# PiBladePsuInput.net
KiCad netlist of a schematic drawn in EAGLE
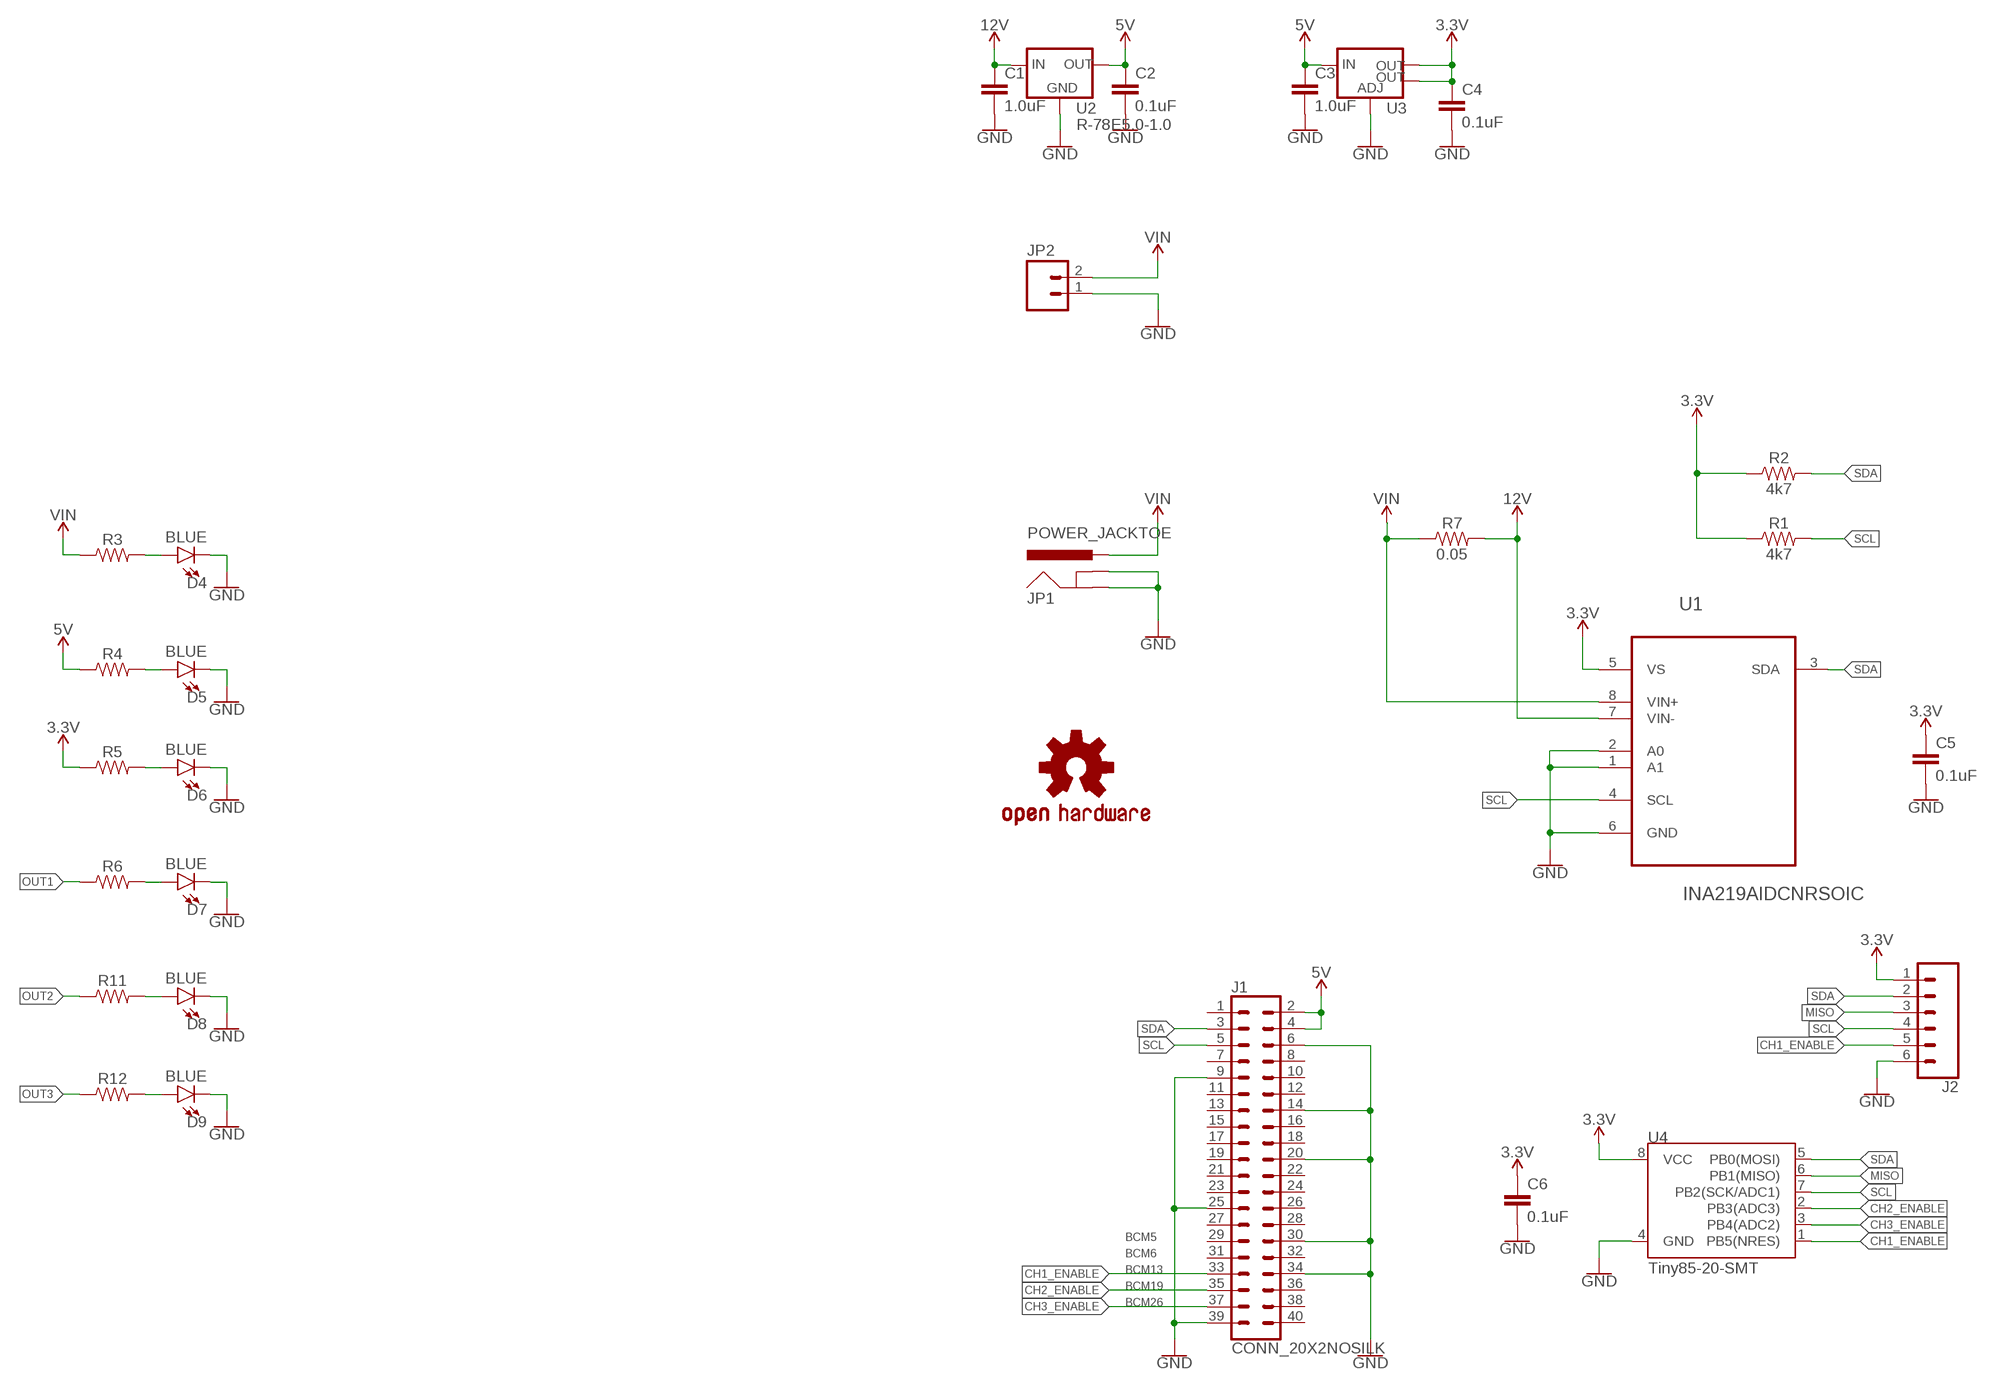
[diagram p0: schematic, sheet 1, part 1 of 2]
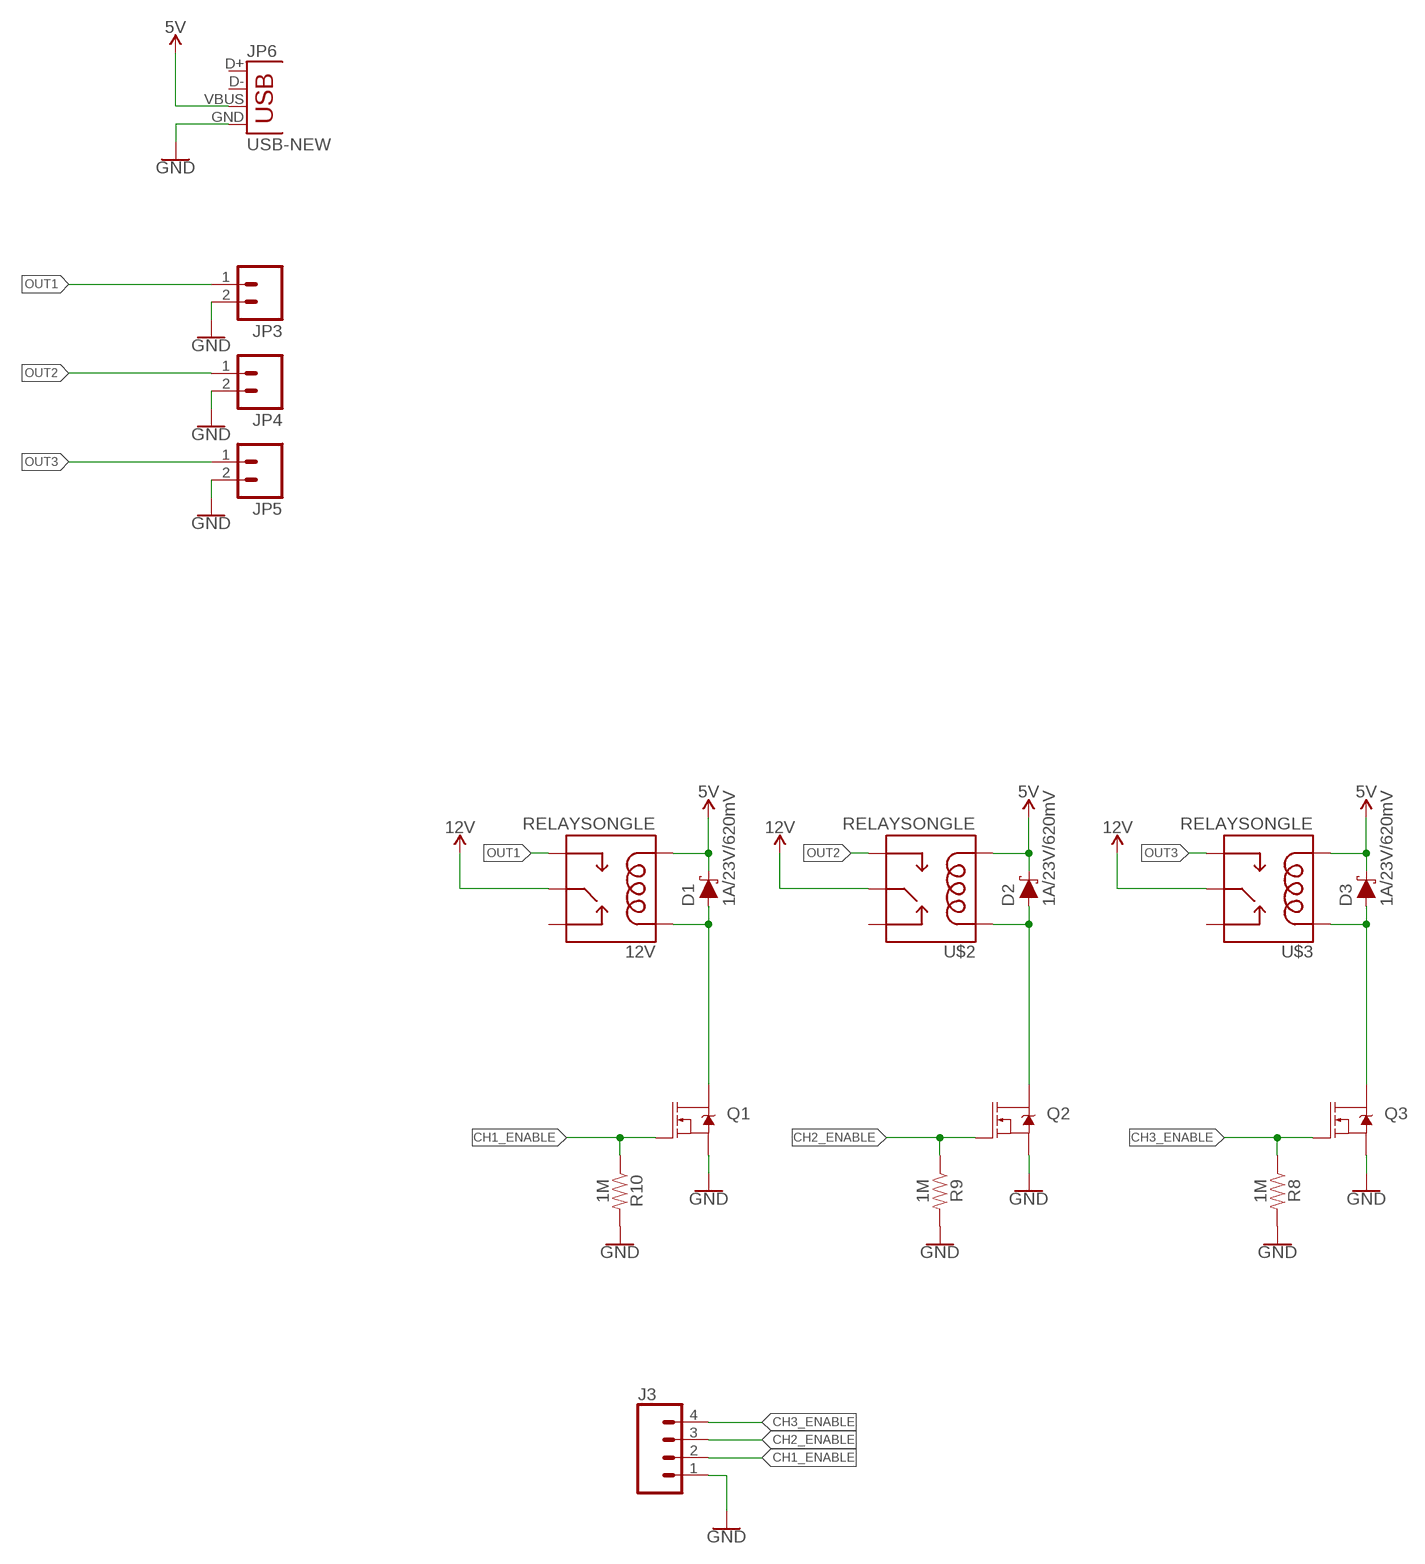
[diagram p1: schematic, sheet 1, part 2 of 2]

(export (version "E")
  (design (tool "Eeschema 10.0.6"))
  (components
    (comp (ref "12V")
      (value "RELAYSONGLE")
      (footprint "eagle-import:SRD-5VDC-SL-C")
      (libsource (lib "eagle-import") (part "RELAYSONGLE"))
    )
    (comp (ref "C1")
      (value "1.0uF")
      (footprint "eagle-import:0805")
      (libsource (lib "eagle-import") (part "1.0UF-0805-25V-(+80/-20%)"))
    )
    (comp (ref "C2")
      (value "0.1uF")
      (footprint "eagle-import:0805")
      (libsource (lib "eagle-import") (part "1.0UF-0805-25V-(+80/-20%)"))
    )
    (comp (ref "C3")
      (value "1.0uF")
      (footprint "eagle-import:0805")
      (libsource (lib "eagle-import") (part "1.0UF-0805-25V-(+80/-20%)"))
    )
    (comp (ref "C4")
      (value "0.1uF")
      (footprint "eagle-import:0805")
      (libsource (lib "eagle-import") (part "1.0UF-0805-25V-(+80/-20%)"))
    )
    (comp (ref "C5")
      (value "0.1uF")
      (footprint "eagle-import:0805")
      (libsource (lib "eagle-import") (part "1.0UF-0805-25V-(+80/-20%)"))
    )
    (comp (ref "C6")
      (value "0.1uF")
      (footprint "eagle-import:0805")
      (libsource (lib "eagle-import") (part "1.0UF-0805-25V-(+80/-20%)"))
    )
    (comp (ref "D1")
      (value "1A/23V/620mV")
      (footprint "eagle-import:SOD-323")
      (libsource (lib "eagle-import") (part "DIODE-SCHOTTKY-BAT20J"))
    )
    (comp (ref "D2")
      (value "1A/23V/620mV")
      (footprint "eagle-import:SOD-323")
      (libsource (lib "eagle-import") (part "DIODE-SCHOTTKY-BAT20J"))
    )
    (comp (ref "D3")
      (value "1A/23V/620mV")
      (footprint "eagle-import:SOD-323")
      (libsource (lib "eagle-import") (part "DIODE-SCHOTTKY-BAT20J"))
    )
    (comp (ref "D4")
      (value "BLUE")
      (footprint "eagle-import:LED-1206")
      (libsource (lib "eagle-import") (part "LED-BLUE1206"))
    )
    (comp (ref "D5")
      (value "BLUE")
      (footprint "eagle-import:LED-1206")
      (libsource (lib "eagle-import") (part "LED-BLUE1206"))
    )
    (comp (ref "D6")
      (value "BLUE")
      (footprint "eagle-import:LED-1206")
      (libsource (lib "eagle-import") (part "LED-BLUE1206"))
    )
    (comp (ref "D7")
      (value "BLUE")
      (footprint "eagle-import:LED-1206")
      (libsource (lib "eagle-import") (part "LED-BLUE1206"))
    )
    (comp (ref "D8")
      (value "BLUE")
      (footprint "eagle-import:LED-1206")
      (libsource (lib "eagle-import") (part "LED-BLUE1206"))
    )
    (comp (ref "D9")
      (value "BLUE")
      (footprint "eagle-import:LED-1206")
      (libsource (lib "eagle-import") (part "LED-BLUE1206"))
    )
    (comp (ref "J1")
      (value "CONN_20X2NOSILK")
      (footprint "eagle-import:2X20_NOSILK")
      (libsource (lib "eagle-import") (part "CONN_20X2NOSILK"))
    )
    (comp (ref "J2")
      (value "CONN_06SMD-1MM")
      (footprint "eagle-import:1X06-1MM")
      (libsource (lib "eagle-import") (part "CONN_06SMD-1MM"))
    )
    (comp (ref "J3")
      (value "CONN_04SMD2")
      (footprint "eagle-import:1X04_1MM_RA")
      (libsource (lib "eagle-import") (part "CONN_04SMD2"))
    )
    (comp (ref "JP1")
      (value "POWER_JACKTOE")
      (footprint "eagle-import:POWER_JACK_SMD_OVERPASTE_TOE")
      (libsource (lib "eagle-import") (part "POWER_JACKTOE"))
    )
    (comp (ref "JP2")
      (value "M025MM")
      (footprint "eagle-import:SCREWTERMINAL-5MM-2")
      (libsource (lib "eagle-import") (part "M025MM"))
    )
    (comp (ref "JP3")
      (value "M025MM")
      (footprint "eagle-import:SCREWTERMINAL-5MM-2")
      (libsource (lib "eagle-import") (part "M025MM"))
    )
    (comp (ref "JP4")
      (value "M025MM")
      (footprint "eagle-import:SCREWTERMINAL-5MM-2")
      (libsource (lib "eagle-import") (part "M025MM"))
    )
    (comp (ref "JP5")
      (value "M025MM")
      (footprint "eagle-import:SCREWTERMINAL-5MM-2")
      (libsource (lib "eagle-import") (part "M025MM"))
    )
    (comp (ref "JP6")
      (value "USB-NEW")
      (footprint "eagle-import:USB-A-VERTICAL")
      (libsource (lib "eagle-import") (part "USB-NEW"))
    )
    (comp (ref "LOGO1")
      (value "OSHW-LOGOM")
      (footprint "eagle-import:OSHW-LOGO-M")
      (libsource (lib "eagle-import") (part "OSHW-LOGOM"))
    )
    (comp (ref "Q1")
      (value "220mA/50V/3.5Ω")
      (footprint "eagle-import:SOT23-3")
      (libsource (lib "eagle-import") (part "MOSFET-NCH-BSS138"))
    )
    (comp (ref "Q2")
      (value "220mA/50V/3.5Ω")
      (footprint "eagle-import:SOT23-3")
      (libsource (lib "eagle-import") (part "MOSFET-NCH-BSS138"))
    )
    (comp (ref "Q3")
      (value "220mA/50V/3.5Ω")
      (footprint "eagle-import:SOT23-3")
      (libsource (lib "eagle-import") (part "MOSFET-NCH-BSS138"))
    )
    (comp (ref "R1")
      (value "4k7")
      (footprint "eagle-import:0805")
      (libsource (lib "eagle-import") (part "RESISTOR0805"))
    )
    (comp (ref "R2")
      (value "4k7")
      (footprint "eagle-import:0805")
      (libsource (lib "eagle-import") (part "RESISTOR0805"))
    )
    (comp (ref "R3")
      (value "RESISTOR0805")
      (footprint "eagle-import:0805")
      (libsource (lib "eagle-import") (part "RESISTOR0805"))
    )
    (comp (ref "R4")
      (value "RESISTOR0805")
      (footprint "eagle-import:0805")
      (libsource (lib "eagle-import") (part "RESISTOR0805"))
    )
    (comp (ref "R5")
      (value "RESISTOR0805")
      (footprint "eagle-import:0805")
      (libsource (lib "eagle-import") (part "RESISTOR0805"))
    )
    (comp (ref "R6")
      (value "RESISTOR0805")
      (footprint "eagle-import:0805")
      (libsource (lib "eagle-import") (part "RESISTOR0805"))
    )
    (comp (ref "R7")
      (value "0.05")
      (footprint "eagle-import:2512")
      (libsource (lib "eagle-import") (part "0.05OHM-2512-3W-1%"))
    )
    (comp (ref "R8")
      (value "1M")
      (footprint "eagle-import:0805")
      (libsource (lib "eagle-import") (part "RESISTOR0805"))
    )
    (comp (ref "R9")
      (value "1M")
      (footprint "eagle-import:0805")
      (libsource (lib "eagle-import") (part "RESISTOR0805"))
    )
    (comp (ref "R10")
      (value "1M")
      (footprint "eagle-import:0805")
      (libsource (lib "eagle-import") (part "RESISTOR0805"))
    )
    (comp (ref "R11")
      (value "RESISTOR0805")
      (footprint "eagle-import:0805")
      (libsource (lib "eagle-import") (part "RESISTOR0805"))
    )
    (comp (ref "R12")
      (value "RESISTOR0805")
      (footprint "eagle-import:0805")
      (libsource (lib "eagle-import") (part "RESISTOR0805"))
    )
    (comp (ref "U$2")
      (value "RELAYSONGLE")
      (footprint "eagle-import:SRD-5VDC-SL-C")
      (libsource (lib "eagle-import") (part "RELAYSONGLE"))
    )
    (comp (ref "U$3")
      (value "RELAYSONGLE")
      (footprint "eagle-import:SRD-5VDC-SL-C")
      (libsource (lib "eagle-import") (part "RELAYSONGLE"))
    )
    (comp (ref "U1")
      (value "INA219AIDCNRSOIC")
      (footprint "eagle-import:SO08")
      (libsource (lib "eagle-import") (part "INA219AIDCNRSOIC"))
    )
    (comp (ref "U2")
      (value "R-78E5.0-1.0")
      (footprint "eagle-import:DC-DC_CONVERTER_78XX")
      (libsource (lib "eagle-import") (part "R-78E5.0-1.0"))
    )
    (comp (ref "U3")
      (value "V_REG_LM1117SOT223")
      (footprint "eagle-import:SOT223")
      (libsource (lib "eagle-import") (part "V_REG_LM1117SOT223"))
    )
    (comp (ref "U4")
      (value "Tiny85-20-SMT")
      (footprint "eagle-import:SO08-EIAJ")
      (libsource (lib "eagle-import") (part "ATTINY45TINY85-20-SMT"))
    )
  )
  (nets
    (net (code "1") (name "3.3V") (class "Default")
      (node (ref "C4") (pin "1") (pinfunction "1_1") (pintype "passive"))
      (node (ref "C5") (pin "1") (pinfunction "1_1") (pintype "passive"))
      (node (ref "C6") (pin "1") (pinfunction "1_1") (pintype "passive"))
      (node (ref "J2") (pin "1") (pinfunction "1_1") (pintype "passive"))
      (node (ref "R1") (pin "1") (pinfunction "1_1") (pintype "passive"))
      (node (ref "R2") (pin "1") (pinfunction "1_1") (pintype "passive"))
      (node (ref "R5") (pin "1") (pinfunction "1_1") (pintype "passive"))
      (node (ref "U1") (pin "5") (pinfunction "VS_5") (pintype "power_in"))
      (node (ref "U3") (pin "2") (pinfunction "OUT_2") (pintype "output"))
      (node (ref "U3") (pin "4") (pinfunction "OUT_4") (pintype "output"))
      (node (ref "U4") (pin "8") (pinfunction "VCC_8") (pintype "bidirectional"))
    )
    (net (code "2") (name "5V") (class "Default")
      (node (ref "12V") (pin "COIL2") (pinfunction "COIL2_COIL2") (pintype "bidirectional"))
      (node (ref "C2") (pin "1") (pinfunction "1_1") (pintype "passive"))
      (node (ref "C3") (pin "1") (pinfunction "1_1") (pintype "passive"))
      (node (ref "D1") (pin "C") (pinfunction "C_C") (pintype "passive"))
      (node (ref "D2") (pin "C") (pinfunction "C_C") (pintype "passive"))
      (node (ref "D3") (pin "C") (pinfunction "C_C") (pintype "passive"))
      (node (ref "J1") (pin "2") (pinfunction "2_2") (pintype "passive"))
      (node (ref "J1") (pin "4") (pinfunction "4_4") (pintype "passive"))
      (node (ref "JP6") (pin "VBUS") (pinfunction "VBUS_VBUS") (pintype "bidirectional"))
      (node (ref "R4") (pin "1") (pinfunction "1_1") (pintype "passive"))
      (node (ref "U$2") (pin "COIL2") (pinfunction "COIL2_COIL2") (pintype "bidirectional"))
      (node (ref "U$3") (pin "COIL2") (pinfunction "COIL2_COIL2") (pintype "bidirectional"))
      (node (ref "U2") (pin "VOUT") (pinfunction "OUT_VOUT") (pintype "passive"))
      (node (ref "U3") (pin "3") (pinfunction "IN_3") (pintype "input"))
    )
    (net (code "3") (name "12V") (class "Default")
      (node (ref "12V") (pin "COMMON") (pinfunction "MAIN_COMMON") (pintype "bidirectional"))
      (node (ref "C1") (pin "1") (pinfunction "1_1") (pintype "passive"))
      (node (ref "R7") (pin "P$2") (pinfunction "2_P$2") (pintype "passive"))
      (node (ref "U$2") (pin "COMMON") (pinfunction "MAIN_COMMON") (pintype "bidirectional"))
      (node (ref "U$3") (pin "COMMON") (pinfunction "MAIN_COMMON") (pintype "bidirectional"))
      (node (ref "U1") (pin "7") (pinfunction "VIN-_7") (pintype "input"))
      (node (ref "U2") (pin "VIN") (pinfunction "IN_VIN") (pintype "input"))
    )
    (net (code "4") (name "CH1_ENABLE") (class "Default")
      (node (ref "J1") (pin "33") (pinfunction "33_33") (pintype "passive"))
      (node (ref "J2") (pin "5") (pinfunction "5_5") (pintype "passive"))
      (node (ref "J3") (pin "2") (pinfunction "2_2") (pintype "passive"))
      (node (ref "Q1") (pin "1") (pinfunction "G_1") (pintype "bidirectional"))
      (node (ref "R10") (pin "1") (pinfunction "1_1") (pintype "passive"))
      (node (ref "U4") (pin "1") (pinfunction "PB5(NRES)_1") (pintype "bidirectional"))
    )
    (net (code "5") (name "CH2_ENABLE") (class "Default")
      (node (ref "J1") (pin "35") (pinfunction "35_35") (pintype "passive"))
      (node (ref "J3") (pin "3") (pinfunction "3_3") (pintype "passive"))
      (node (ref "Q2") (pin "1") (pinfunction "G_1") (pintype "bidirectional"))
      (node (ref "R9") (pin "1") (pinfunction "1_1") (pintype "passive"))
      (node (ref "U4") (pin "2") (pinfunction "PB3(ADC3)_2") (pintype "bidirectional"))
    )
    (net (code "6") (name "CH3_ENABLE") (class "Default")
      (node (ref "J1") (pin "37") (pinfunction "37_37") (pintype "passive"))
      (node (ref "J3") (pin "4") (pinfunction "4_4") (pintype "passive"))
      (node (ref "Q3") (pin "1") (pinfunction "G_1") (pintype "bidirectional"))
      (node (ref "R8") (pin "1") (pinfunction "1_1") (pintype "passive"))
      (node (ref "U4") (pin "3") (pinfunction "PB4(ADC2)_3") (pintype "bidirectional"))
    )
    (net (code "7") (name "GND") (class "Default")
      (node (ref "C1") (pin "2") (pinfunction "2_2") (pintype "passive"))
      (node (ref "C2") (pin "2") (pinfunction "2_2") (pintype "passive"))
      (node (ref "C3") (pin "2") (pinfunction "2_2") (pintype "passive"))
      (node (ref "C4") (pin "2") (pinfunction "2_2") (pintype "passive"))
      (node (ref "C5") (pin "2") (pinfunction "2_2") (pintype "passive"))
      (node (ref "C6") (pin "2") (pinfunction "2_2") (pintype "passive"))
      (node (ref "D4") (pin "C") (pinfunction "C_C") (pintype "passive"))
      (node (ref "D5") (pin "C") (pinfunction "C_C") (pintype "passive"))
      (node (ref "D6") (pin "C") (pinfunction "C_C") (pintype "passive"))
      (node (ref "D7") (pin "C") (pinfunction "C_C") (pintype "passive"))
      (node (ref "D8") (pin "C") (pinfunction "C_C") (pintype "passive"))
      (node (ref "D9") (pin "C") (pinfunction "C_C") (pintype "passive"))
      (node (ref "J1") (pin "14") (pinfunction "14_14") (pintype "passive"))
      (node (ref "J1") (pin "20") (pinfunction "20_20") (pintype "passive"))
      (node (ref "J1") (pin "25") (pinfunction "25_25") (pintype "passive"))
      (node (ref "J1") (pin "30") (pinfunction "30_30") (pintype "passive"))
      (node (ref "J1") (pin "34") (pinfunction "34_34") (pintype "passive"))
      (node (ref "J1") (pin "39") (pinfunction "39_39") (pintype "passive"))
      (node (ref "J1") (pin "6") (pinfunction "6_6") (pintype "passive"))
      (node (ref "J1") (pin "9") (pinfunction "9_9") (pintype "passive"))
      (node (ref "J2") (pin "6") (pinfunction "6_6") (pintype "passive"))
      (node (ref "J3") (pin "1") (pinfunction "1_1") (pintype "passive"))
      (node (ref "JP1") (pin "GND") (pinfunction "GNDBREAK_GND") (pintype "bidirectional"))
      (node (ref "JP1") (pin "P$4") (pinfunction "GND_P$4") (pintype "bidirectional"))
      (node (ref "JP2") (pin "1") (pinfunction "1_1") (pintype "passive"))
      (node (ref "JP3") (pin "2") (pinfunction "2_2") (pintype "passive"))
      (node (ref "JP4") (pin "2") (pinfunction "2_2") (pintype "passive"))
      (node (ref "JP5") (pin "2") (pinfunction "2_2") (pintype "passive"))
      (node (ref "JP6") (pin "GND") (pinfunction "GND_GND") (pintype "bidirectional"))
      (node (ref "Q1") (pin "2") (pinfunction "S_2") (pintype "bidirectional"))
      (node (ref "Q2") (pin "2") (pinfunction "S_2") (pintype "bidirectional"))
      (node (ref "Q3") (pin "2") (pinfunction "S_2") (pintype "bidirectional"))
      (node (ref "R10") (pin "2") (pinfunction "2_2") (pintype "passive"))
      (node (ref "R8") (pin "2") (pinfunction "2_2") (pintype "passive"))
      (node (ref "R9") (pin "2") (pinfunction "2_2") (pintype "passive"))
      (node (ref "U1") (pin "1") (pinfunction "A1_1") (pintype "input"))
      (node (ref "U1") (pin "2") (pinfunction "A0_2") (pintype "input"))
      (node (ref "U1") (pin "6") (pinfunction "GND_6") (pintype "passive"))
      (node (ref "U2") (pin "GND") (pinfunction "GND_GND") (pintype "input"))
      (node (ref "U3") (pin "1") (pinfunction "ADJ_1") (pintype "input"))
      (node (ref "U4") (pin "4") (pinfunction "GND_4") (pintype "bidirectional"))
    )
    (net (code "8") (name "MISO") (class "Default")
      (node (ref "J2") (pin "3") (pinfunction "3_3") (pintype "passive"))
      (node (ref "U4") (pin "6") (pinfunction "PB1(MISO)_6") (pintype "bidirectional"))
    )
    (net (code "9") (name "Net-(D4-PadA)") (class "Default")
      (node (ref "D4") (pin "A") (pinfunction "A_A") (pintype "passive"))
      (node (ref "R3") (pin "2") (pinfunction "2_2") (pintype "passive"))
    )
    (net (code "10") (name "Net-(D5-PadA)") (class "Default")
      (node (ref "D5") (pin "A") (pinfunction "A_A") (pintype "passive"))
      (node (ref "R4") (pin "2") (pinfunction "2_2") (pintype "passive"))
    )
    (net (code "11") (name "Net-(D6-PadA)") (class "Default")
      (node (ref "D6") (pin "A") (pinfunction "A_A") (pintype "passive"))
      (node (ref "R5") (pin "2") (pinfunction "2_2") (pintype "passive"))
    )
    (net (code "12") (name "Net-(D7-PadA)") (class "Default")
      (node (ref "D7") (pin "A") (pinfunction "A_A") (pintype "passive"))
      (node (ref "R6") (pin "2") (pinfunction "2_2") (pintype "passive"))
    )
    (net (code "13") (name "Net-(D8-PadA)") (class "Default")
      (node (ref "D8") (pin "A") (pinfunction "A_A") (pintype "passive"))
      (node (ref "R11") (pin "2") (pinfunction "2_2") (pintype "passive"))
    )
    (net (code "14") (name "Net-(D9-PadA)") (class "Default")
      (node (ref "D9") (pin "A") (pinfunction "A_A") (pintype "passive"))
      (node (ref "R12") (pin "2") (pinfunction "2_2") (pintype "passive"))
    )
    (net (code "15") (name "Net-(Q1-D)") (class "Default")
      (node (ref "12V") (pin "COIL1") (pinfunction "COIL1_COIL1") (pintype "bidirectional"))
      (node (ref "D1") (pin "A") (pinfunction "A_A") (pintype "passive"))
      (node (ref "Q1") (pin "3") (pinfunction "D_3") (pintype "bidirectional"))
    )
    (net (code "16") (name "Net-(Q2-D)") (class "Default")
      (node (ref "D2") (pin "A") (pinfunction "A_A") (pintype "passive"))
      (node (ref "Q2") (pin "3") (pinfunction "D_3") (pintype "bidirectional"))
      (node (ref "U$2") (pin "COIL1") (pinfunction "COIL1_COIL1") (pintype "bidirectional"))
    )
    (net (code "17") (name "Net-(Q3-D)") (class "Default")
      (node (ref "D3") (pin "A") (pinfunction "A_A") (pintype "passive"))
      (node (ref "Q3") (pin "3") (pinfunction "D_3") (pintype "bidirectional"))
      (node (ref "U$3") (pin "COIL1") (pinfunction "COIL1_COIL1") (pintype "bidirectional"))
    )
    (net (code "18") (name "OUT1") (class "Default")
      (node (ref "12V") (pin "OPEN") (pinfunction "NO_OPEN") (pintype "bidirectional"))
      (node (ref "JP3") (pin "1") (pinfunction "1_1") (pintype "passive"))
      (node (ref "R6") (pin "1") (pinfunction "1_1") (pintype "passive"))
    )
    (net (code "19") (name "OUT2") (class "Default")
      (node (ref "JP4") (pin "1") (pinfunction "1_1") (pintype "passive"))
      (node (ref "R11") (pin "1") (pinfunction "1_1") (pintype "passive"))
      (node (ref "U$2") (pin "OPEN") (pinfunction "NO_OPEN") (pintype "bidirectional"))
    )
    (net (code "20") (name "OUT3") (class "Default")
      (node (ref "JP5") (pin "1") (pinfunction "1_1") (pintype "passive"))
      (node (ref "R12") (pin "1") (pinfunction "1_1") (pintype "passive"))
      (node (ref "U$3") (pin "OPEN") (pinfunction "NO_OPEN") (pintype "bidirectional"))
    )
    (net (code "21") (name "SCL") (class "Default")
      (node (ref "J1") (pin "5") (pinfunction "5_5") (pintype "passive"))
      (node (ref "J2") (pin "4") (pinfunction "4_4") (pintype "passive"))
      (node (ref "R1") (pin "2") (pinfunction "2_2") (pintype "passive"))
      (node (ref "U1") (pin "4") (pinfunction "SCL_4") (pintype "input"))
      (node (ref "U4") (pin "7") (pinfunction "PB2(SCK/ADC1)_7") (pintype "bidirectional"))
    )
    (net (code "22") (name "SDA") (class "Default")
      (node (ref "J1") (pin "3") (pinfunction "3_3") (pintype "passive"))
      (node (ref "J2") (pin "2") (pinfunction "2_2") (pintype "passive"))
      (node (ref "R2") (pin "2") (pinfunction "2_2") (pintype "passive"))
      (node (ref "U1") (pin "3") (pinfunction "SDA_3") (pintype "bidirectional"))
      (node (ref "U4") (pin "5") (pinfunction "PB0(MOSI)_5") (pintype "bidirectional"))
    )
    (net (code "23") (name "VIN") (class "Default")
      (node (ref "JP1") (pin "VIN0") (pinfunction "PWR_VIN0") (pintype "bidirectional"))
      (node (ref "JP2") (pin "2") (pinfunction "2_2") (pintype "passive"))
      (node (ref "R3") (pin "1") (pinfunction "1_1") (pintype "passive"))
      (node (ref "R7") (pin "P$1") (pinfunction "1_P$1") (pintype "passive"))
      (node (ref "U1") (pin "8") (pinfunction "VIN+_8") (pintype "input"))
    )
    (net (code "24") (name "unconnected-(12V-NC-PadCLOSED)") (class "Default")
      (node (ref "12V") (pin "CLOSED") (pinfunction "NC_CLOSED") (pintype "bidirectional"))
    )
    (net (code "25") (name "unconnected-(J1-Pad1)") (class "Default")
      (node (ref "J1") (pin "1") (pinfunction "1_1") (pintype "passive"))
    )
    (net (code "26") (name "unconnected-(J1-Pad7)") (class "Default")
      (node (ref "J1") (pin "7") (pinfunction "7_7") (pintype "passive"))
    )
    (net (code "27") (name "unconnected-(J1-Pad8)") (class "Default")
      (node (ref "J1") (pin "8") (pinfunction "8_8") (pintype "passive"))
    )
    (net (code "28") (name "unconnected-(J1-Pad10)") (class "Default")
      (node (ref "J1") (pin "10") (pinfunction "10_10") (pintype "passive"))
    )
    (net (code "29") (name "unconnected-(J1-Pad11)") (class "Default")
      (node (ref "J1") (pin "11") (pinfunction "11_11") (pintype "passive"))
    )
    (net (code "30") (name "unconnected-(J1-Pad12)") (class "Default")
      (node (ref "J1") (pin "12") (pinfunction "12_12") (pintype "passive"))
    )
    (net (code "31") (name "unconnected-(J1-Pad13)") (class "Default")
      (node (ref "J1") (pin "13") (pinfunction "13_13") (pintype "passive"))
    )
    (net (code "32") (name "unconnected-(J1-Pad15)") (class "Default")
      (node (ref "J1") (pin "15") (pinfunction "15_15") (pintype "passive"))
    )
    (net (code "33") (name "unconnected-(J1-Pad16)") (class "Default")
      (node (ref "J1") (pin "16") (pinfunction "16_16") (pintype "passive"))
    )
    (net (code "34") (name "unconnected-(J1-Pad17)") (class "Default")
      (node (ref "J1") (pin "17") (pinfunction "17_17") (pintype "passive"))
    )
    (net (code "35") (name "unconnected-(J1-Pad18)") (class "Default")
      (node (ref "J1") (pin "18") (pinfunction "18_18") (pintype "passive"))
    )
    (net (code "36") (name "unconnected-(J1-Pad19)") (class "Default")
      (node (ref "J1") (pin "19") (pinfunction "19_19") (pintype "passive"))
    )
    (net (code "37") (name "unconnected-(J1-Pad21)") (class "Default")
      (node (ref "J1") (pin "21") (pinfunction "21_21") (pintype "passive"))
    )
    (net (code "38") (name "unconnected-(J1-Pad22)") (class "Default")
      (node (ref "J1") (pin "22") (pinfunction "22_22") (pintype "passive"))
    )
    (net (code "39") (name "unconnected-(J1-Pad23)") (class "Default")
      (node (ref "J1") (pin "23") (pinfunction "23_23") (pintype "passive"))
    )
    (net (code "40") (name "unconnected-(J1-Pad24)") (class "Default")
      (node (ref "J1") (pin "24") (pinfunction "24_24") (pintype "passive"))
    )
    (net (code "41") (name "unconnected-(J1-Pad26)") (class "Default")
      (node (ref "J1") (pin "26") (pinfunction "26_26") (pintype "passive"))
    )
    (net (code "42") (name "unconnected-(J1-Pad27)") (class "Default")
      (node (ref "J1") (pin "27") (pinfunction "27_27") (pintype "passive"))
    )
    (net (code "43") (name "unconnected-(J1-Pad28)") (class "Default")
      (node (ref "J1") (pin "28") (pinfunction "28_28") (pintype "passive"))
    )
    (net (code "44") (name "unconnected-(J1-Pad29)") (class "Default")
      (node (ref "J1") (pin "29") (pinfunction "29_29") (pintype "passive"))
    )
    (net (code "45") (name "unconnected-(J1-Pad31)") (class "Default")
      (node (ref "J1") (pin "31") (pinfunction "31_31") (pintype "passive"))
    )
    (net (code "46") (name "unconnected-(J1-Pad32)") (class "Default")
      (node (ref "J1") (pin "32") (pinfunction "32_32") (pintype "passive"))
    )
    (net (code "47") (name "unconnected-(J1-Pad36)") (class "Default")
      (node (ref "J1") (pin "36") (pinfunction "36_36") (pintype "passive"))
    )
    (net (code "48") (name "unconnected-(J1-Pad38)") (class "Default")
      (node (ref "J1") (pin "38") (pinfunction "38_38") (pintype "passive"))
    )
    (net (code "49") (name "unconnected-(J1-Pad40)") (class "Default")
      (node (ref "J1") (pin "40") (pinfunction "40_40") (pintype "passive"))
    )
    (net (code "50") (name "unconnected-(JP6-PadD+)") (class "Default")
      (node (ref "JP6") (pin "D+") (pinfunction "D+_D+") (pintype "bidirectional"))
    )
    (net (code "51") (name "unconnected-(JP6-PadD-)") (class "Default")
      (node (ref "JP6") (pin "D-") (pinfunction "D-_D-") (pintype "bidirectional"))
    )
    (net (code "52") (name "unconnected-(U$2-NC-PadCLOSED)") (class "Default")
      (node (ref "U$2") (pin "CLOSED") (pinfunction "NC_CLOSED") (pintype "bidirectional"))
    )
    (net (code "53") (name "unconnected-(U$3-NC-PadCLOSED)") (class "Default")
      (node (ref "U$3") (pin "CLOSED") (pinfunction "NC_CLOSED") (pintype "bidirectional"))
    )
  )
)
